# SP26_FindingTitan_Filt_post_Amp_Michael_.net
KiCad netlist of a schematic drawn in Altium Designer
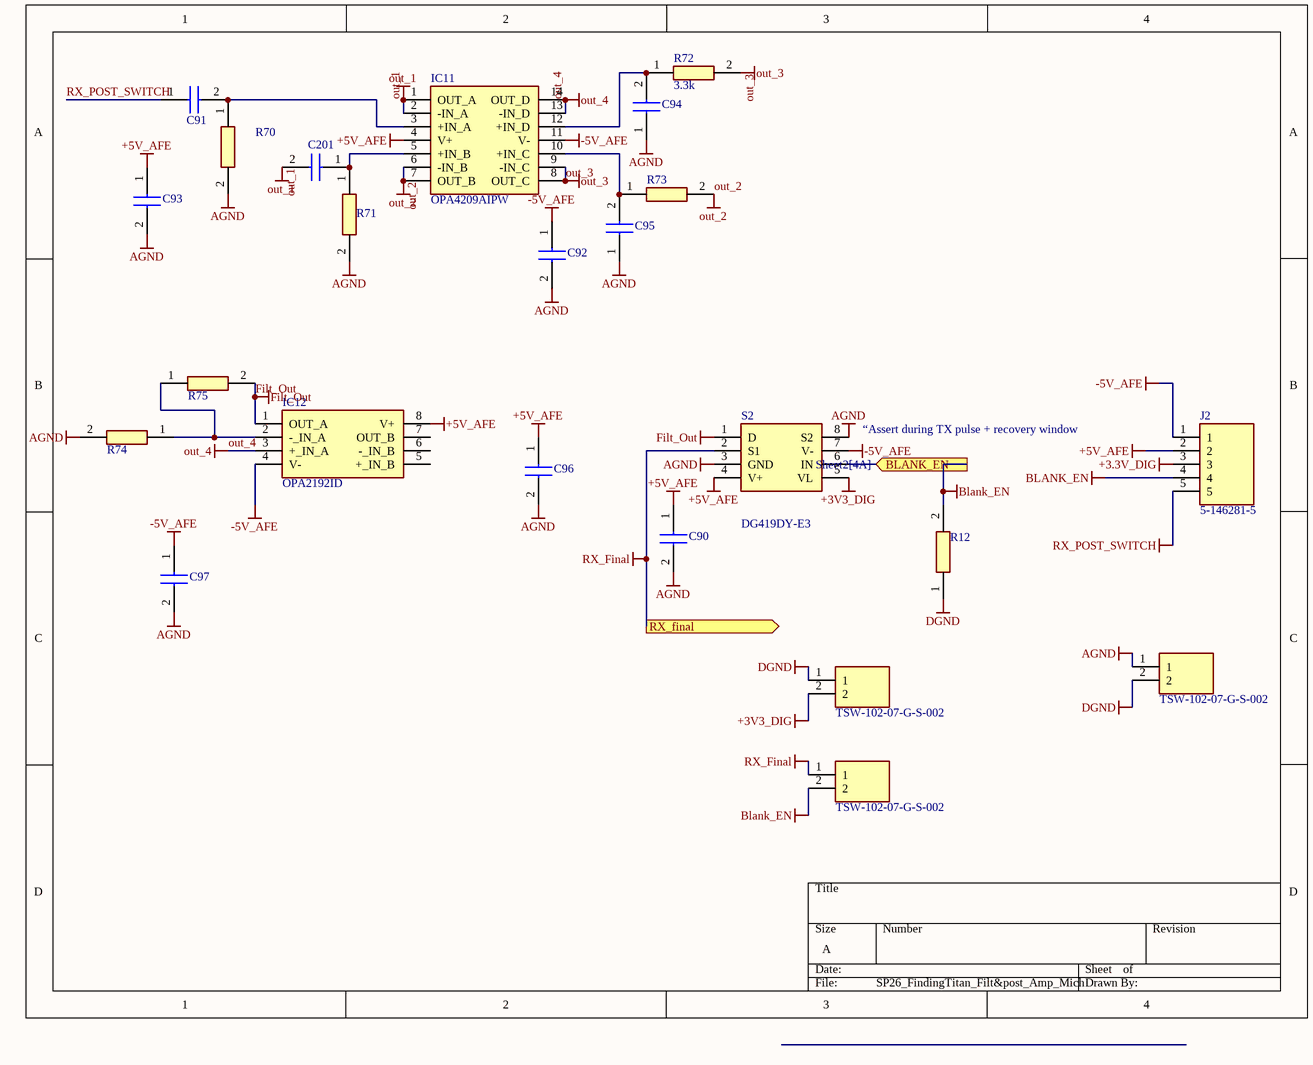
[diagram p0: SP26_FindingTitan_Filt&post_Amp_Michael_Krueger.SchDoc]

(export (version "E")
  (design (tool "Eeschema 10.0.6"))
  (components
    (comp (ref "C90")
      (value "GRM188R71H104KA93B")
      (footprint "SamacSys:CAPC1608X90N")
      (description "Capacitor")
      (libsource (lib "*") (part "GRM188R71H104KA93B"))
    )
    (comp (ref "C91")
      (value "GCM1885C1H103JA16D")
      (footprint "SamacSys:CAPC1608X90N")
      (description "Capacitor")
      (libsource (lib "*") (part "GCM1885C1H103JA16D"))
    )
    (comp (ref "C92")
      (value "GRM188R71H104KA93B")
      (footprint "SamacSys:CAPC1608X90N")
      (description "Capacitor")
      (libsource (lib "*") (part "GRM188R71H104KA93B"))
    )
    (comp (ref "C93")
      (value "GRM188R71H104KA93B")
      (footprint "SamacSys:CAPC1608X90N")
      (description "Capacitor")
      (libsource (lib "*") (part "GRM188R71H104KA93B"))
    )
    (comp (ref "C94")
      (value "GCM1885C1H103JA16D")
      (footprint "SamacSys:CAPC1608X90N")
      (description "Capacitor")
      (libsource (lib "*") (part "GCM1885C1H103JA16D"))
    )
    (comp (ref "C95")
      (value "GCM1885C1H103JA16D")
      (footprint "SamacSys:CAPC1608X90N")
      (description "Capacitor")
      (libsource (lib "*") (part "GCM1885C1H103JA16D"))
    )
    (comp (ref "C96")
      (value "GRM188R71H104KA93B")
      (footprint "SamacSys:CAPC1608X90N")
      (description "Capacitor")
      (libsource (lib "*") (part "GRM188R71H104KA93B"))
    )
    (comp (ref "C97")
      (value "GRM188R71H104KA93B")
      (footprint "SamacSys:CAPC1608X90N")
      (description "Capacitor")
      (libsource (lib "*") (part "GRM188R71H104KA93B"))
    )
    (comp (ref "C201")
      (value "GCM1885C1H103JA16D")
      (footprint "SamacSys:CAPC1608X90N")
      (description "Capacitor")
      (libsource (lib "*") (part "GCM1885C1H103JA16D"))
    )
    (comp (ref "IC11")
      (value "OPA4209AIPW")
      (footprint "SamacSys:SOP65P640X120-14N")
      (description "Integrated Circuit")
      (fields (field (name "MOUSER PART NUMBER") "595-OPA4209AIPW"))
      (libsource (lib "*") (part "OPA4209AIPW"))
    )
    (comp (ref "IC12")
      (value "OPA2192ID")
      (footprint "SamacSys:SOIC127P600X175-8N")
      (description "Integrated Circuit")
      (fields (field (name "MOUSER PART NUMBER") "595-OPA2192ID"))
      (libsource (lib "*") (part "OPA2192ID"))
    )
    (comp (ref "J0")
      (value "TSW-102-07-G-S-002")
      (footprint "SamacSys:HDRV2W64P0X254_1X2_508X254X838P")
      (description "Connector")
      (fields (field (name "MOUSER PART NUMBER") "200-TSW-10207GS002"))
      (libsource (lib "*") (part "TSW-102-07-G-S-002"))
    )
    (comp (ref "J2")
      (value "5-146281-5")
      (footprint "SamacSys:HDRV5W67P0X254_1X5_1229X234X821P")
      (description "Connector")
      (fields (field (name "MOUSER PART NUMBER") "571-5-146281-5"))
      (libsource (lib "*") (part "5-146281-5"))
    )
    (comp (ref "J22")
      (value "TSW-102-07-G-S-002")
      (footprint "SamacSys:HDRV2W64P0X254_1X2_508X254X838P")
      (description "Connector")
      (fields (field (name "MOUSER PART NUMBER") "200-TSW-10207GS002"))
      (libsource (lib "*") (part "TSW-102-07-G-S-002"))
    )
    (comp (ref "J69")
      (value "TSW-102-07-G-S-002")
      (footprint "SamacSys:HDRV2W64P0X254_1X2_508X254X838P")
      (description "Connector")
      (fields (field (name "MOUSER PART NUMBER") "200-TSW-10207GS002"))
      (libsource (lib "*") (part "TSW-102-07-G-S-002"))
    )
    (comp (ref "R12")
      (value "TNPW0805100KBEEA")
      (footprint "SamacSys:RESC2012X55N")
      (description "Resistor")
      (fields (field (name "MOUSER PART NUMBER") "71-TNPW0805100KBEEA"))
      (libsource (lib "*") (part "TNPW0805100KBEEA"))
    )
    (comp (ref "R70")
      (value "20k")
      (footprint "SamacSys:RESC1608X60N")
      (description "Resistor")
      (fields
        (field (name "MANUFACTURER_PART_NUMBER") "RR0816P-103-D")
        (field (name "MOUSER PART NUMBER") "754-RR0816P-103D")
      )
      (libsource (lib "") (part "RR0816P-103-D_1"))
    )
    (comp (ref "R71")
      (value "20k")
      (footprint "SamacSys:RESC1608X60N")
      (description "Resistor")
      (fields
        (field (name "MANUFACTURER_PART_NUMBER") "RR0816P-103-D")
        (field (name "MOUSER PART NUMBER") "754-RR0816P-103D")
      )
      (libsource (lib "") (part "RR0816P-103-D_1"))
    )
    (comp (ref "R72")
      (value "3.3k")
      (footprint "SamacSys:RESC1608X60N")
      (description "Resistor")
      (fields
        (field (name "MANUFACTURER_PART_NUMBER") "RR0816P-104-D")
        (field (name "MOUSER PART NUMBER") "754-RR0816P-104D")
      )
      (libsource (lib "*") (part "RR0816P-104-D"))
    )
    (comp (ref "R73")
      (value "3.3k")
      (footprint "SamacSys:RESC1608X60N")
      (description "Resistor")
      (fields
        (field (name "MANUFACTURER_PART_NUMBER") "RR0816P-104-D")
        (field (name "MOUSER PART NUMBER") "754-RR0816P-104D")
      )
      (libsource (lib "*") (part "RR0816P-104-D"))
    )
    (comp (ref "R74")
      (value "20k")
      (footprint "SamacSys:RESC1608X60N")
      (description "Resistor")
      (fields
        (field (name "MANUFACTURER_PART_NUMBER") "RR0816P-103-D")
        (field (name "MOUSER PART NUMBER") "754-RR0816P-103D")
      )
      (libsource (lib "*") (part "RR0816P-103-D"))
    )
    (comp (ref "R75")
      (value "20k")
      (footprint "SamacSys:RESC1608X60N")
      (description "Resistor")
      (fields
        (field (name "MANUFACTURER_PART_NUMBER") "RR0816P-103-D")
        (field (name "MOUSER PART NUMBER") "754-RR0816P-103D")
      )
      (libsource (lib "") (part "RR0816P-103-D_2"))
    )
    (comp (ref "S2")
      (value "DG419DY-E3")
      (footprint "SamacSys:SOIC127P600X175-8N")
      (description "Switch")
      (fields (field (name "MOUSER PART NUMBER") "781-DG419DY-E3"))
      (libsource (lib "*") (part "DG419DY-E3"))
    )
  )
  (nets
    (net (code "1") (name "+3.3V_DIG") (class "Default")
      (node (ref "J2") (pin "3") (pinfunction "3_3") (pintype "passive"))
    )
    (net (code "2") (name "+3V3_DIG") (class "Default")
      (node (ref "J69") (pin "2") (pinfunction "2_2") (pintype "passive"))
      (node (ref "S2") (pin "5") (pinfunction "VL_5") (pintype "passive"))
    )
    (net (code "3") (name "+5V_AFE") (class "Default")
      (node (ref "C90") (pin "1") (pinfunction "1_1") (pintype "passive"))
      (node (ref "C93") (pin "1") (pinfunction "1_1") (pintype "passive"))
      (node (ref "C96") (pin "1") (pinfunction "1_1") (pintype "passive"))
      (node (ref "IC11") (pin "4") (pinfunction "V+_4") (pintype "passive"))
      (node (ref "IC12") (pin "8") (pinfunction "V+_8") (pintype "passive"))
      (node (ref "J2") (pin "2") (pinfunction "2_2") (pintype "passive"))
      (node (ref "S2") (pin "4") (pinfunction "V+_4") (pintype "passive"))
    )
    (net (code "4") (name "-5V_AFE") (class "Default")
      (node (ref "C92") (pin "1") (pinfunction "1_1") (pintype "passive"))
      (node (ref "C97") (pin "1") (pinfunction "1_1") (pintype "passive"))
      (node (ref "IC11") (pin "11") (pinfunction "V-_11") (pintype "passive"))
      (node (ref "IC12") (pin "4") (pinfunction "V-_4") (pintype "passive"))
      (node (ref "J2") (pin "1") (pinfunction "1_1") (pintype "passive"))
      (node (ref "S2") (pin "7") (pinfunction "V-_7") (pintype "passive"))
    )
    (net (code "5") (name "AGND") (class "Default")
      (node (ref "C90") (pin "2") (pinfunction "2_2") (pintype "passive"))
      (node (ref "C92") (pin "2") (pinfunction "2_2") (pintype "passive"))
      (node (ref "C93") (pin "2") (pinfunction "2_2") (pintype "passive"))
      (node (ref "C94") (pin "1") (pinfunction "1_1") (pintype "passive"))
      (node (ref "C95") (pin "1") (pinfunction "1_1") (pintype "passive"))
      (node (ref "C96") (pin "2") (pinfunction "2_2") (pintype "passive"))
      (node (ref "C97") (pin "2") (pinfunction "2_2") (pintype "passive"))
      (node (ref "J22") (pin "1") (pinfunction "1_1") (pintype "passive"))
      (node (ref "R70") (pin "2") (pinfunction "R2_2") (pintype "passive"))
      (node (ref "R71") (pin "2") (pinfunction "R2_2") (pintype "passive"))
      (node (ref "R74") (pin "2") (pinfunction "R2_2") (pintype "passive"))
      (node (ref "S2") (pin "3") (pinfunction "GND_3") (pintype "passive"))
      (node (ref "S2") (pin "8") (pinfunction "S2_8") (pintype "passive"))
    )
    (net (code "6") (name "BLANK_EN") (class "Default")
      (node (ref "J0") (pin "2") (pinfunction "2_2") (pintype "passive"))
      (node (ref "J2") (pin "4") (pinfunction "4_4") (pintype "passive"))
      (node (ref "R12") (pin "2") (pinfunction "2_2") (pintype "passive"))
      (node (ref "S2") (pin "6") (pinfunction "IN_6") (pintype "passive"))
    )
    (net (code "7") (name "DGND") (class "Default")
      (node (ref "J22") (pin "2") (pinfunction "2_2") (pintype "passive"))
      (node (ref "J69") (pin "1") (pinfunction "1_1") (pintype "passive"))
      (node (ref "R12") (pin "1") (pinfunction "1_1") (pintype "passive"))
    )
    (net (code "8") (name "Filt_Out") (class "Default")
      (node (ref "IC12") (pin "1") (pinfunction "OUT_A_1") (pintype "passive"))
      (node (ref "R75") (pin "2") (pinfunction "R2_2") (pintype "passive"))
      (node (ref "S2") (pin "1") (pinfunction "D_1") (pintype "passive"))
    )
    (net (code "9") (name "Net-(IC11-+IN_A)") (class "Default")
      (node (ref "C91") (pin "2") (pinfunction "2_2") (pintype "passive"))
      (node (ref "IC11") (pin "3") (pinfunction "+IN_A_3") (pintype "passive"))
      (node (ref "R70") (pin "1") (pinfunction "R1_1") (pintype "passive"))
    )
    (net (code "10") (name "Net-(IC11-+IN_B)") (class "Default")
      (node (ref "C201") (pin "1") (pinfunction "1_1") (pintype "passive"))
      (node (ref "IC11") (pin "5") (pinfunction "+IN_B_5") (pintype "passive"))
      (node (ref "R71") (pin "1") (pinfunction "R1_1") (pintype "passive"))
    )
    (net (code "11") (name "Net-(IC11-+IN_C)") (class "Default")
      (node (ref "C95") (pin "2") (pinfunction "2_2") (pintype "passive"))
      (node (ref "IC11") (pin "10") (pinfunction "+IN_C_10") (pintype "passive"))
      (node (ref "R73") (pin "1") (pinfunction "R1_1") (pintype "passive"))
    )
    (net (code "12") (name "Net-(IC11-+IN_D)") (class "Default")
      (node (ref "C94") (pin "2") (pinfunction "2_2") (pintype "passive"))
      (node (ref "IC11") (pin "12") (pinfunction "+IN_D_12") (pintype "passive"))
      (node (ref "R72") (pin "1") (pinfunction "R1_1") (pintype "passive"))
    )
    (net (code "13") (name "Net-(IC12--_IN_A)") (class "Default")
      (node (ref "IC12") (pin "2") (pinfunction "-_IN_A_2") (pintype "passive"))
      (node (ref "R74") (pin "1") (pinfunction "R1_1") (pintype "passive"))
      (node (ref "R75") (pin "1") (pinfunction "R1_1") (pintype "passive"))
    )
    (net (code "14") (name "RX_Final") (class "Default")
      (node (ref "J0") (pin "1") (pinfunction "1_1") (pintype "passive"))
      (node (ref "S2") (pin "2") (pinfunction "S1_2") (pintype "passive"))
    )
    (net (code "15") (name "RX_POST_SWITCH") (class "Default")
      (node (ref "C91") (pin "1") (pinfunction "1_1") (pintype "passive"))
      (node (ref "J2") (pin "5") (pinfunction "5_5") (pintype "passive"))
    )
    (net (code "16") (name "out_1") (class "Default")
      (node (ref "C201") (pin "2") (pinfunction "2_2") (pintype "passive"))
      (node (ref "IC11") (pin "1") (pinfunction "OUT_A_1") (pintype "passive"))
      (node (ref "IC11") (pin "2") (pinfunction "-IN_A_2") (pintype "passive"))
    )
    (net (code "17") (name "out_2") (class "Default")
      (node (ref "IC11") (pin "6") (pinfunction "-IN_B_6") (pintype "passive"))
      (node (ref "IC11") (pin "7") (pinfunction "OUT_B_7") (pintype "passive"))
      (node (ref "R73") (pin "2") (pinfunction "R2_2") (pintype "passive"))
    )
    (net (code "18") (name "out_3") (class "Default")
      (node (ref "IC11") (pin "8") (pinfunction "OUT_C_8") (pintype "passive"))
      (node (ref "IC11") (pin "9") (pinfunction "-IN_C_9") (pintype "passive"))
      (node (ref "R72") (pin "2") (pinfunction "R2_2") (pintype "passive"))
    )
    (net (code "19") (name "out_4") (class "Default")
      (node (ref "IC11") (pin "13") (pinfunction "-IN_D_13") (pintype "passive"))
      (node (ref "IC11") (pin "14") (pinfunction "OUT_D_14") (pintype "passive"))
      (node (ref "IC12") (pin "3") (pinfunction "+_IN_A_3") (pintype "passive"))
    )
    (net (code "20") (name "unconnected-(IC12-+_IN_B-Pad5)") (class "Default")
      (node (ref "IC12") (pin "5") (pinfunction "+_IN_B_5") (pintype "passive"))
    )
    (net (code "21") (name "unconnected-(IC12--_IN_B-Pad6)") (class "Default")
      (node (ref "IC12") (pin "6") (pinfunction "-_IN_B_6") (pintype "passive"))
    )
    (net (code "22") (name "unconnected-(IC12-OUT_B-Pad7)") (class "Default")
      (node (ref "IC12") (pin "7") (pinfunction "OUT_B_7") (pintype "passive"))
    )
  )
)
